# LibreSolar_BMS48V_0.net
KiCad netlist of a schematic drawn in Altium Designer
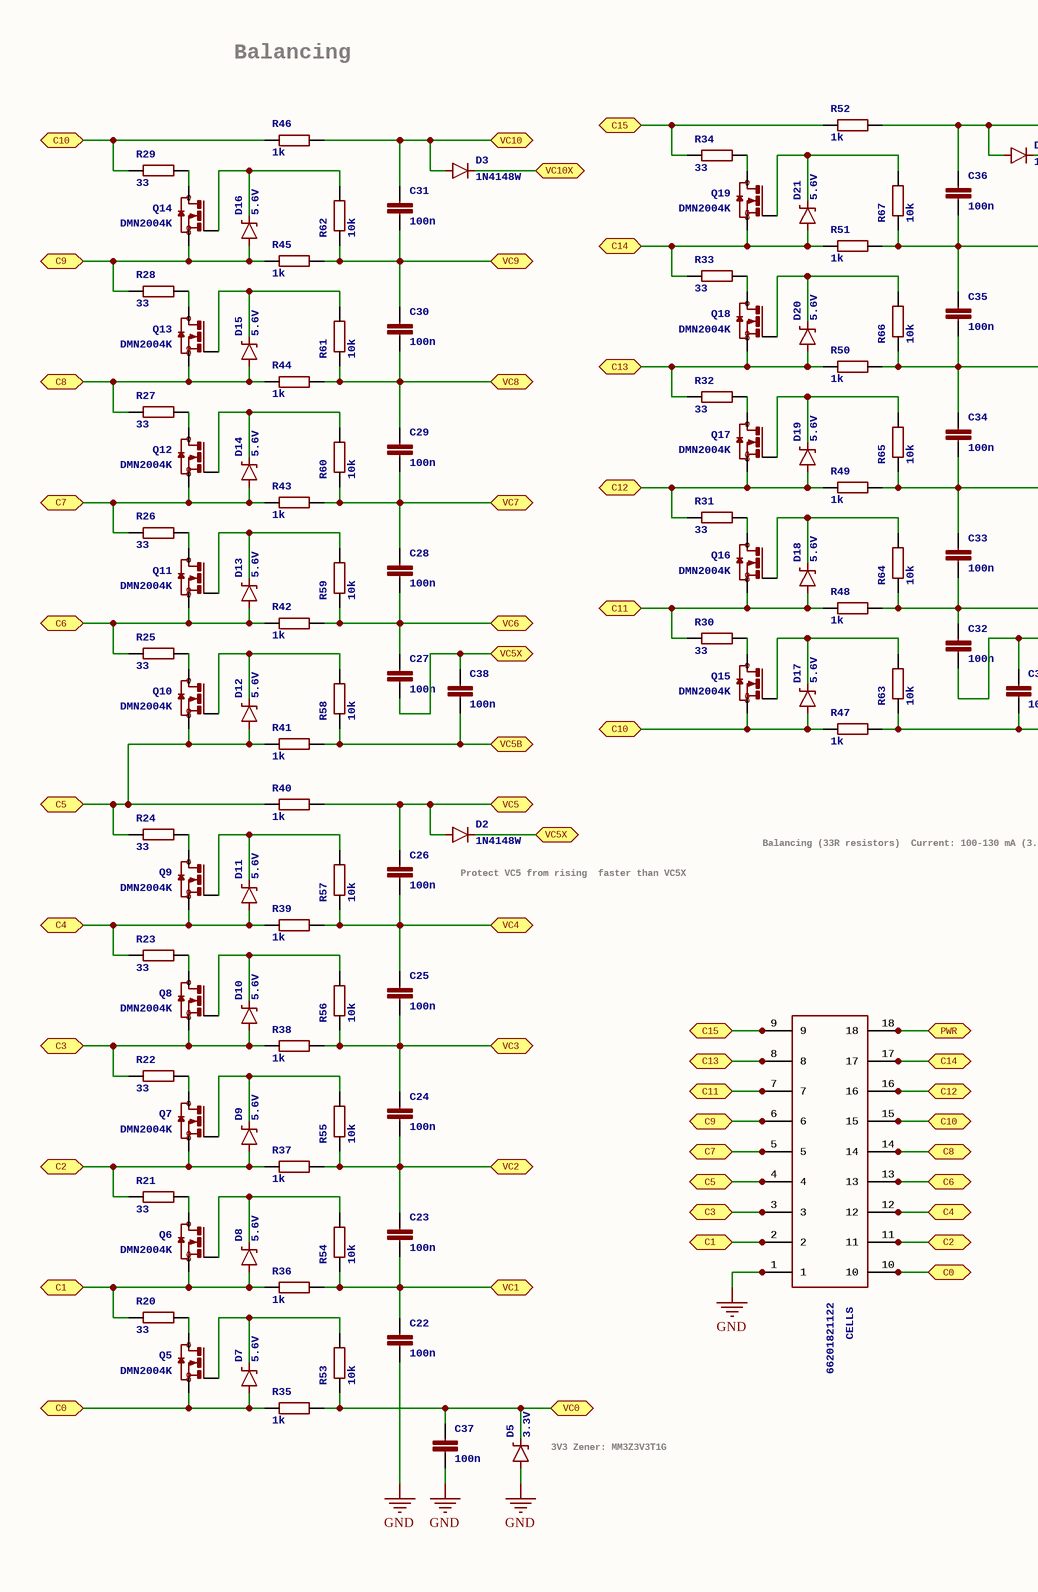
[diagram p0: LibreSolar_BMS48V_0.SchDoc, left]
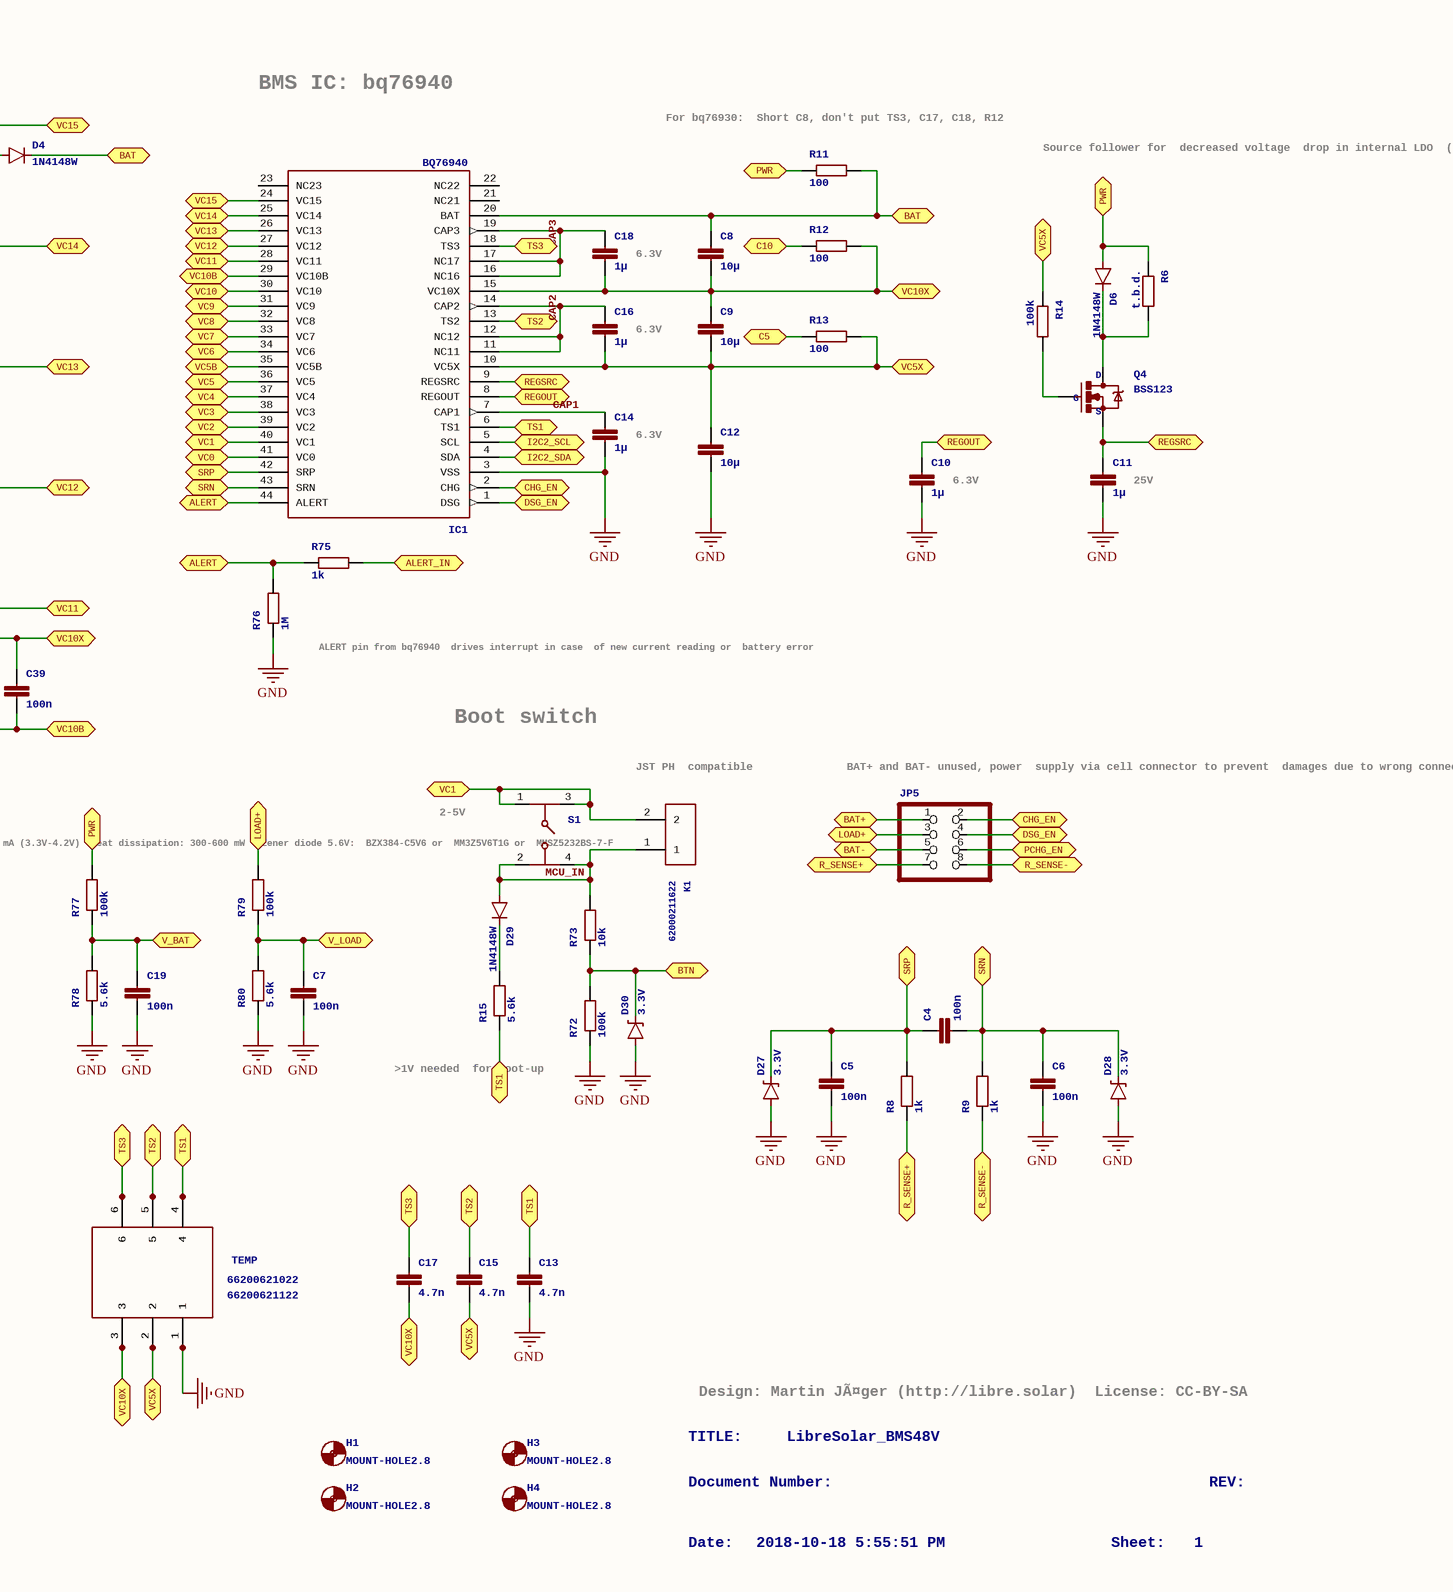
[diagram p1: LibreSolar_BMS48V_0.SchDoc, right]

(export (version "E")
  (design (tool "Eeschema 10.0.6"))
  (components
    (comp (ref "C4")
      (value "100n")
      (footprint "C0603")
      (description "CAPACITOR, European symbol")
      (fields (field (name "MF") "WALSIN") (field (name "MPN") "0603B104K500CT"))
      (libsource (lib "") (part "C-EUC0603_1"))
    )
    (comp (ref "C5")
      (value "100n")
      (footprint "C0603")
      (description "CAPACITOR, European symbol")
      (fields (field (name "MF") "WALSIN") (field (name "MPN") "0603B104K500CT"))
      (libsource (lib "rcl") (part "C-EUC0603"))
    )
    (comp (ref "C6")
      (value "100n")
      (footprint "C0603")
      (description "CAPACITOR, European symbol")
      (fields (field (name "MF") "WALSIN") (field (name "MPN") "0603B104K500CT"))
      (libsource (lib "rcl") (part "C-EUC0603"))
    )
    (comp (ref "C7")
      (value "100n")
      (footprint "C0603")
      (description "CAPACITOR, European symbol")
      (fields (field (name "MF") "WALSIN") (field (name "MPN") "0603B104K500CT"))
      (libsource (lib "rcl") (part "C-EUC0603"))
    )
    (comp (ref "C8")
      (value "10µ")
      (footprint "C1210")
      (description "CAPACITOR, European symbol")
      (fields (field (name "MF") "MURATA") (field (name "MPN") "GRM32ER7YA106KA12L"))
      (libsource (lib "rcl") (part "C-EUC1210"))
    )
    (comp (ref "C9")
      (value "10µ")
      (footprint "C1210")
      (description "CAPACITOR, European symbol")
      (fields (field (name "MF") "MURATA") (field (name "MPN") "GRM32ER7YA106KA12L"))
      (libsource (lib "rcl") (part "C-EUC1210"))
    )
    (comp (ref "C10")
      (value "1µ")
      (footprint "C0603")
      (description "CAPACITOR, European symbol")
      (fields (field (name "MF") "AVX") (field (name "MPN") "0805YC475KAT2A"))
      (libsource (lib "rcl") (part "C-EUC0603"))
    )
    (comp (ref "C11")
      (value "1µ")
      (footprint "C0603")
      (description "CAPACITOR, European symbol")
      (fields (field (name "MF") "MURATA") (field (name "MPN") "GRM188R71E105KA12D"))
      (libsource (lib "rcl") (part "C-EUC0603"))
    )
    (comp (ref "C12")
      (value "10µ")
      (footprint "C1210")
      (description "CAPACITOR, European symbol")
      (fields (field (name "MF") "MURATA") (field (name "MPN") "GRM32ER7YA106KA12L"))
      (libsource (lib "rcl") (part "C-EUC1210"))
    )
    (comp (ref "C13")
      (value "4.7n")
      (footprint "C0603")
      (description "CAPACITOR, European symbol")
      (fields (field (name "MF") "WALSIN") (field (name "MPN") "0603B104K500CT"))
      (libsource (lib "rcl") (part "C-EUC0603"))
    )
    (comp (ref "C14")
      (value "1µ")
      (footprint "C0603")
      (description "CAPACITOR, European symbol")
      (fields (field (name "MF") "MURATA") (field (name "MPN") "GRM188R71E105KA12D"))
      (libsource (lib "rcl") (part "C-EUC0603"))
    )
    (comp (ref "C15")
      (value "4.7n")
      (footprint "C0603")
      (description "CAPACITOR, European symbol")
      (fields (field (name "MF") "WALSIN") (field (name "MPN") "0603B104K500CT"))
      (libsource (lib "rcl") (part "C-EUC0603"))
    )
    (comp (ref "C16")
      (value "1µ")
      (footprint "C0603")
      (description "CAPACITOR, European symbol")
      (fields (field (name "MF") "MURATA") (field (name "MPN") "GRM188R71E105KA12D"))
      (libsource (lib "rcl") (part "C-EUC0603"))
    )
    (comp (ref "C17")
      (value "4.7n")
      (footprint "C0603")
      (description "CAPACITOR, European symbol")
      (fields (field (name "MF") "WALSIN") (field (name "MPN") "0603B104K500CT"))
      (libsource (lib "rcl") (part "C-EUC0603"))
    )
    (comp (ref "C18")
      (value "1µ")
      (footprint "C0603")
      (description "CAPACITOR, European symbol")
      (fields (field (name "MF") "MURATA") (field (name "MPN") "GRM188R71E105KA12D"))
      (libsource (lib "rcl") (part "C-EUC0603"))
    )
    (comp (ref "C19")
      (value "100n")
      (footprint "C0603")
      (description "CAPACITOR, European symbol")
      (fields (field (name "MF") "WALSIN") (field (name "MPN") "0603B104K500CT"))
      (libsource (lib "rcl") (part "C-EUC0603"))
    )
    (comp (ref "C22")
      (value "100n")
      (footprint "C0603")
      (description "CAPACITOR, European symbol")
      (fields (field (name "MF") "WALSIN") (field (name "MPN") "0603B104K500CT"))
      (libsource (lib "rcl") (part "C-EUC0603"))
    )
    (comp (ref "C23")
      (value "100n")
      (footprint "C0603")
      (description "CAPACITOR, European symbol")
      (fields (field (name "MF") "WALSIN") (field (name "MPN") "0603B104K500CT"))
      (libsource (lib "rcl") (part "C-EUC0603"))
    )
    (comp (ref "C24")
      (value "100n")
      (footprint "C0603")
      (description "CAPACITOR, European symbol")
      (fields (field (name "MF") "WALSIN") (field (name "MPN") "0603B104K500CT"))
      (libsource (lib "rcl") (part "C-EUC0603"))
    )
    (comp (ref "C25")
      (value "100n")
      (footprint "C0603")
      (description "CAPACITOR, European symbol")
      (fields (field (name "MF") "WALSIN") (field (name "MPN") "0603B104K500CT"))
      (libsource (lib "rcl") (part "C-EUC0603"))
    )
    (comp (ref "C26")
      (value "100n")
      (footprint "C0603")
      (description "CAPACITOR, European symbol")
      (fields (field (name "MF") "WALSIN") (field (name "MPN") "0603B104K500CT"))
      (libsource (lib "rcl") (part "C-EUC0603"))
    )
    (comp (ref "C27")
      (value "100n")
      (footprint "C0603")
      (description "CAPACITOR, European symbol")
      (fields (field (name "MF") "WALSIN") (field (name "MPN") "0603B104K500CT"))
      (libsource (lib "rcl") (part "C-EUC0603"))
    )
    (comp (ref "C28")
      (value "100n")
      (footprint "C0603")
      (description "CAPACITOR, European symbol")
      (fields (field (name "MF") "WALSIN") (field (name "MPN") "0603B104K500CT"))
      (libsource (lib "rcl") (part "C-EUC0603"))
    )
    (comp (ref "C29")
      (value "100n")
      (footprint "C0603")
      (description "CAPACITOR, European symbol")
      (fields (field (name "MF") "WALSIN") (field (name "MPN") "0603B104K500CT"))
      (libsource (lib "rcl") (part "C-EUC0603"))
    )
    (comp (ref "C30")
      (value "100n")
      (footprint "C0603")
      (description "CAPACITOR, European symbol")
      (fields (field (name "MF") "WALSIN") (field (name "MPN") "0603B104K500CT"))
      (libsource (lib "rcl") (part "C-EUC0603"))
    )
    (comp (ref "C31")
      (value "100n")
      (footprint "C0603")
      (description "CAPACITOR, European symbol")
      (fields (field (name "MF") "WALSIN") (field (name "MPN") "0603B104K500CT"))
      (libsource (lib "rcl") (part "C-EUC0603"))
    )
    (comp (ref "C32")
      (value "100n")
      (footprint "C0603")
      (description "CAPACITOR, European symbol")
      (fields (field (name "MF") "WALSIN") (field (name "MPN") "0603B104K500CT"))
      (libsource (lib "rcl") (part "C-EUC0603"))
    )
    (comp (ref "C33")
      (value "100n")
      (footprint "C0603")
      (description "CAPACITOR, European symbol")
      (fields (field (name "MF") "WALSIN") (field (name "MPN") "0603B104K500CT"))
      (libsource (lib "rcl") (part "C-EUC0603"))
    )
    (comp (ref "C34")
      (value "100n")
      (footprint "C0603")
      (description "CAPACITOR, European symbol")
      (fields (field (name "MF") "WALSIN") (field (name "MPN") "0603B104K500CT"))
      (libsource (lib "rcl") (part "C-EUC0603"))
    )
    (comp (ref "C35")
      (value "100n")
      (footprint "C0603")
      (description "CAPACITOR, European symbol")
      (fields (field (name "MF") "WALSIN") (field (name "MPN") "0603B104K500CT"))
      (libsource (lib "rcl") (part "C-EUC0603"))
    )
    (comp (ref "C36")
      (value "100n")
      (footprint "C0603")
      (description "CAPACITOR, European symbol")
      (fields (field (name "MF") "WALSIN") (field (name "MPN") "0603B104K500CT"))
      (libsource (lib "rcl") (part "C-EUC0603"))
    )
    (comp (ref "C37")
      (value "100n")
      (footprint "C0603")
      (description "CAPACITOR, European symbol")
      (fields (field (name "MF") "WALSIN") (field (name "MPN") "0603B104K500CT"))
      (libsource (lib "rcl") (part "C-EUC0603"))
    )
    (comp (ref "C38")
      (value "100n")
      (footprint "C0603")
      (description "CAPACITOR, European symbol")
      (fields (field (name "MF") "WALSIN") (field (name "MPN") "0603B104K500CT"))
      (libsource (lib "rcl") (part "C-EUC0603"))
    )
    (comp (ref "C39")
      (value "100n")
      (footprint "C0603")
      (description "CAPACITOR, European symbol")
      (fields (field (name "MF") "WALSIN") (field (name "MPN") "0603B104K500CT"))
      (libsource (lib "rcl") (part "C-EUC0603"))
    )
    (comp (ref "CELLS")
      (value "66201821022")
      (footprint "66201821022")
      (libsource (lib "Wire_to_Board_Connectors_rev15d") (part "66201821022"))
    )
    (comp (ref "D2")
      (value "1N4148W")
      (footprint "SOD-123")
      (fields (field (name "MF") "DIODES INC.") (field (name "MPN") "1N4148W-7-F."))
      (libsource (lib "SparkFun-DiscreteSemi") (part "DIODESOD123"))
    )
    (comp (ref "D3")
      (value "1N4148W")
      (footprint "SOD-123")
      (fields (field (name "MF") "DIODES INC.") (field (name "MPN") "1N4148W-7-F."))
      (libsource (lib "SparkFun-DiscreteSemi") (part "DIODESOD123"))
    )
    (comp (ref "D4")
      (value "1N4148W")
      (footprint "SOD-123")
      (fields (field (name "MF") "DIODES INC.") (field (name "MPN") "1N4148W-7-F."))
      (libsource (lib "SparkFun-DiscreteSemi") (part "DIODESOD123"))
    )
    (comp (ref "D5")
      (value "3.3V")
      (footprint "SOD-323")
      (description "Zener Diode Production Part - 8199 3.4V Zener Voltage")
      (fields (field (name "MF") "NXP") (field (name "MPN") "BZX384-C5V6"))
      (libsource (lib "SparkFun-DiscreteSemi") (part "DIODE-ZENER5.6V"))
    )
    (comp (ref "D6")
      (value "1N4148W")
      (footprint "SOD-123")
      (fields (field (name "MF") "DIODES INC.") (field (name "MPN") "1N4148W-7-F."))
      (libsource (lib "SparkFun-DiscreteSemi") (part "DIODESOD123"))
    )
    (comp (ref "D7")
      (value "5.6V")
      (footprint "SOD-323")
      (description "Zener Diode Production Part - 8199 3.4V Zener Voltage")
      (fields (field (name "MF") "NXP") (field (name "MPN") "BZX384-C5V6"))
      (libsource (lib "SparkFun-DiscreteSemi") (part "DIODE-ZENER5.6V"))
    )
    (comp (ref "D8")
      (value "5.6V")
      (footprint "SOD-323")
      (description "Zener Diode Production Part - 8199 3.4V Zener Voltage")
      (fields (field (name "MF") "NXP") (field (name "MPN") "BZX384-C5V6"))
      (libsource (lib "SparkFun-DiscreteSemi") (part "DIODE-ZENER5.6V"))
    )
    (comp (ref "D9")
      (value "5.6V")
      (footprint "SOD-323")
      (description "Zener Diode Production Part - 8199 3.4V Zener Voltage")
      (fields (field (name "MF") "NXP") (field (name "MPN") "BZX384-C5V6"))
      (libsource (lib "SparkFun-DiscreteSemi") (part "DIODE-ZENER5.6V"))
    )
    (comp (ref "D10")
      (value "5.6V")
      (footprint "SOD-323")
      (description "Zener Diode Production Part - 8199 3.4V Zener Voltage")
      (fields (field (name "MF") "NXP") (field (name "MPN") "BZX384-C5V6"))
      (libsource (lib "SparkFun-DiscreteSemi") (part "DIODE-ZENER5.6V"))
    )
    (comp (ref "D11")
      (value "5.6V")
      (footprint "SOD-323")
      (description "Zener Diode Production Part - 8199 3.4V Zener Voltage")
      (fields (field (name "MF") "NXP") (field (name "MPN") "BZX384-C5V6"))
      (libsource (lib "SparkFun-DiscreteSemi") (part "DIODE-ZENER5.6V"))
    )
    (comp (ref "D12")
      (value "5.6V")
      (footprint "SOD-323")
      (description "Zener Diode Production Part - 8199 3.4V Zener Voltage")
      (fields (field (name "MF") "NXP") (field (name "MPN") "BZX384-C5V6"))
      (libsource (lib "SparkFun-DiscreteSemi") (part "DIODE-ZENER5.6V"))
    )
    (comp (ref "D13")
      (value "5.6V")
      (footprint "SOD-323")
      (description "Zener Diode Production Part - 8199 3.4V Zener Voltage")
      (fields (field (name "MF") "NXP") (field (name "MPN") "BZX384-C5V6"))
      (libsource (lib "SparkFun-DiscreteSemi") (part "DIODE-ZENER5.6V"))
    )
    (comp (ref "D14")
      (value "5.6V")
      (footprint "SOD-323")
      (description "Zener Diode Production Part - 8199 3.4V Zener Voltage")
      (fields (field (name "MF") "NXP") (field (name "MPN") "BZX384-C5V6"))
      (libsource (lib "SparkFun-DiscreteSemi") (part "DIODE-ZENER5.6V"))
    )
    (comp (ref "D15")
      (value "5.6V")
      (footprint "SOD-323")
      (description "Zener Diode Production Part - 8199 3.4V Zener Voltage")
      (fields (field (name "MF") "NXP") (field (name "MPN") "BZX384-C5V6"))
      (libsource (lib "SparkFun-DiscreteSemi") (part "DIODE-ZENER5.6V"))
    )
    (comp (ref "D16")
      (value "5.6V")
      (footprint "SOD-323")
      (description "Zener Diode Production Part - 8199 3.4V Zener Voltage")
      (fields (field (name "MF") "NXP") (field (name "MPN") "BZX384-C5V6"))
      (libsource (lib "SparkFun-DiscreteSemi") (part "DIODE-ZENER5.6V"))
    )
    (comp (ref "D17")
      (value "5.6V")
      (footprint "SOD-323")
      (description "Zener Diode Production Part - 8199 3.4V Zener Voltage")
      (fields (field (name "MF") "NXP") (field (name "MPN") "BZX384-C5V6"))
      (libsource (lib "SparkFun-DiscreteSemi") (part "DIODE-ZENER5.6V"))
    )
    (comp (ref "D18")
      (value "5.6V")
      (footprint "SOD-323")
      (description "Zener Diode Production Part - 8199 3.4V Zener Voltage")
      (fields (field (name "MF") "NXP") (field (name "MPN") "BZX384-C5V6"))
      (libsource (lib "SparkFun-DiscreteSemi") (part "DIODE-ZENER5.6V"))
    )
    (comp (ref "D19")
      (value "5.6V")
      (footprint "SOD-323")
      (description "Zener Diode Production Part - 8199 3.4V Zener Voltage")
      (fields (field (name "MF") "NXP") (field (name "MPN") "BZX384-C5V6"))
      (libsource (lib "SparkFun-DiscreteSemi") (part "DIODE-ZENER5.6V"))
    )
    (comp (ref "D20")
      (value "5.6V")
      (footprint "SOD-323")
      (description "Zener Diode Production Part - 8199 3.4V Zener Voltage")
      (fields (field (name "MF") "NXP") (field (name "MPN") "BZX384-C5V6"))
      (libsource (lib "SparkFun-DiscreteSemi") (part "DIODE-ZENER5.6V"))
    )
    (comp (ref "D21")
      (value "5.6V")
      (footprint "SOD-323")
      (description "Zener Diode Production Part - 8199 3.4V Zener Voltage")
      (fields (field (name "MF") "NXP") (field (name "MPN") "BZX384-C5V6"))
      (libsource (lib "SparkFun-DiscreteSemi") (part "DIODE-ZENER5.6V"))
    )
    (comp (ref "D27")
      (value "3.3V")
      (footprint "SOD-323")
      (description "Zener Diode Production Part - 8199 3.4V Zener Voltage")
      (fields (field (name "MF") "NXP") (field (name "MPN") "BZX384-C5V6"))
      (libsource (lib "SparkFun-DiscreteSemi") (part "DIODE-ZENER5.6V"))
    )
    (comp (ref "D28")
      (value "3.3V")
      (footprint "SOD-323")
      (description "Zener Diode Production Part - 8199 3.4V Zener Voltage")
      (fields (field (name "MF") "NXP") (field (name "MPN") "BZX384-C5V6"))
      (libsource (lib "SparkFun-DiscreteSemi") (part "DIODE-ZENER5.6V"))
    )
    (comp (ref "D29")
      (value "1N4148W")
      (footprint "SOD-123")
      (fields (field (name "MF") "DIODES INC.") (field (name "MPN") "1N4148W-7-F."))
      (libsource (lib "SparkFun-DiscreteSemi") (part "DIODESOD123"))
    )
    (comp (ref "D30")
      (value "3.3V")
      (footprint "SOD-323")
      (description "Zener Diode Production Part - 8199 3.4V Zener Voltage")
      (fields (field (name "MF") "NXP") (field (name "MPN") "BZX384-C5V6"))
      (libsource (lib "SparkFun-DiscreteSemi") (part "DIODE-ZENER5.6V"))
    )
    (comp (ref "H1")
      (value "MOUNT-HOLE2.8")
      (footprint "2,8")
      (description "MOUNTING HOLE with drill center marker")
      (libsource (lib "holes") (part "MOUNT-HOLE2.8"))
    )
    (comp (ref "H2")
      (value "MOUNT-HOLE2.8")
      (footprint "2,8")
      (description "MOUNTING HOLE with drill center marker")
      (libsource (lib "holes") (part "MOUNT-HOLE2.8"))
    )
    (comp (ref "H3")
      (value "MOUNT-HOLE2.8")
      (footprint "2,8")
      (description "MOUNTING HOLE with drill center marker")
      (libsource (lib "holes") (part "MOUNT-HOLE2.8"))
    )
    (comp (ref "H4")
      (value "MOUNT-HOLE2.8")
      (footprint "2,8")
      (description "MOUNTING HOLE with drill center marker")
      (libsource (lib "holes") (part "MOUNT-HOLE2.8"))
    )
    (comp (ref "IC1")
      (value "BQ76940")
      (footprint "TSSOP44")
      (fields (field (name "MF") "TEXAS INSTRUMENTS") (field (name "MPN") "BQ7694003DBT"))
      (libsource (lib "LibreSolar") (part "BQ76940"))
    )
    (comp (ref "JP5")
      (value "PINHD-2X4")
      (footprint "2X04")
      (description "PIN HEADER")
      (fields (field (name "LIBRARYNAME") "pinhead"))
      (libsource (lib "pinhead") (part "PINHD-2X4"))
    )
    (comp (ref "K1")
      (value "62000211622")
      (footprint "62000211622")
      (libsource (lib "Wire_to_Board_Connectors_rev15d") (part "62000211622"))
    )
    (comp (ref "K4")
      (value "66200621122")
      (footprint "66200621122")
      (libsource (lib "Wire_to_Board_Connectors_rev15d") (part "66200621122"))
    )
    (comp (ref "K5")
      (value "66201821122")
      (footprint "66201821122")
      (libsource (lib "Wire_to_Board_Connectors_rev15d") (part "66201821122"))
    )
    (comp (ref "Q4")
      (value "BSS123")
      (footprint "SOT23-3")
      (fields
        (field (name "MF") "NXP")
        (field (name "MPN") "2N7002,215")
        (field (name "D") "D")
        (field (name "S") "S")
        (field (name "G") "G")
      )
      (libsource (lib "SparkFun-DiscreteSemi") (part "MOSFET-NCHANNELBSS138"))
    )
    (comp (ref "Q5")
      (value "DMN2004K")
      (footprint "SOT23")
      (description "N-CHANNEL MOS FET with low VGS and ESD protection")
      (fields
        (field (name "MF") "DIODES INC.")
        (field (name "MPN") "DMN2004K-7")
        (field (name "LIBRARYNAME") "resolut")
      )
      (libsource (lib "resolut") (part "DMN2004K"))
    )
    (comp (ref "Q6")
      (value "DMN2004K")
      (footprint "SOT23")
      (description "N-CHANNEL MOS FET with low VGS and ESD protection")
      (fields
        (field (name "MF") "DIODES INC.")
        (field (name "MPN") "DMN2004K-7")
        (field (name "LIBRARYNAME") "resolut")
      )
      (libsource (lib "resolut") (part "DMN2004K"))
    )
    (comp (ref "Q7")
      (value "DMN2004K")
      (footprint "SOT23")
      (description "N-CHANNEL MOS FET with low VGS and ESD protection")
      (fields
        (field (name "MF") "DIODES INC.")
        (field (name "MPN") "DMN2004K-7")
        (field (name "LIBRARYNAME") "resolut")
      )
      (libsource (lib "resolut") (part "DMN2004K"))
    )
    (comp (ref "Q8")
      (value "DMN2004K")
      (footprint "SOT23")
      (description "N-CHANNEL MOS FET with low VGS and ESD protection")
      (fields
        (field (name "MF") "DIODES INC.")
        (field (name "MPN") "DMN2004K-7")
        (field (name "LIBRARYNAME") "resolut")
      )
      (libsource (lib "resolut") (part "DMN2004K"))
    )
    (comp (ref "Q9")
      (value "DMN2004K")
      (footprint "SOT23")
      (description "N-CHANNEL MOS FET with low VGS and ESD protection")
      (fields
        (field (name "MF") "DIODES INC.")
        (field (name "MPN") "DMN2004K-7")
        (field (name "LIBRARYNAME") "resolut")
      )
      (libsource (lib "resolut") (part "DMN2004K"))
    )
    (comp (ref "Q10")
      (value "DMN2004K")
      (footprint "SOT23")
      (description "N-CHANNEL MOS FET with low VGS and ESD protection")
      (fields
        (field (name "MF") "DIODES INC.")
        (field (name "MPN") "DMN2004K-7")
        (field (name "LIBRARYNAME") "resolut")
      )
      (libsource (lib "resolut") (part "DMN2004K"))
    )
    (comp (ref "Q11")
      (value "DMN2004K")
      (footprint "SOT23")
      (description "N-CHANNEL MOS FET with low VGS and ESD protection")
      (fields
        (field (name "MF") "DIODES INC.")
        (field (name "MPN") "DMN2004K-7")
        (field (name "LIBRARYNAME") "resolut")
      )
      (libsource (lib "resolut") (part "DMN2004K"))
    )
    (comp (ref "Q12")
      (value "DMN2004K")
      (footprint "SOT23")
      (description "N-CHANNEL MOS FET with low VGS and ESD protection")
      (fields
        (field (name "MF") "DIODES INC.")
        (field (name "MPN") "DMN2004K-7")
        (field (name "LIBRARYNAME") "resolut")
      )
      (libsource (lib "resolut") (part "DMN2004K"))
    )
    (comp (ref "Q13")
      (value "DMN2004K")
      (footprint "SOT23")
      (description "N-CHANNEL MOS FET with low VGS and ESD protection")
      (fields
        (field (name "MF") "DIODES INC.")
        (field (name "MPN") "DMN2004K-7")
        (field (name "LIBRARYNAME") "resolut")
      )
      (libsource (lib "resolut") (part "DMN2004K"))
    )
    (comp (ref "Q14")
      (value "DMN2004K")
      (footprint "SOT23")
      (description "N-CHANNEL MOS FET with low VGS and ESD protection")
      (fields
        (field (name "MF") "DIODES INC.")
        (field (name "MPN") "DMN2004K-7")
        (field (name "LIBRARYNAME") "resolut")
      )
      (libsource (lib "resolut") (part "DMN2004K"))
    )
    (comp (ref "Q15")
      (value "DMN2004K")
      (footprint "SOT23")
      (description "N-CHANNEL MOS FET with low VGS and ESD protection")
      (fields
        (field (name "MF") "DIODES INC.")
        (field (name "MPN") "DMN2004K-7")
        (field (name "LIBRARYNAME") "resolut")
      )
      (libsource (lib "resolut") (part "DMN2004K"))
    )
    (comp (ref "Q16")
      (value "DMN2004K")
      (footprint "SOT23")
      (description "N-CHANNEL MOS FET with low VGS and ESD protection")
      (fields
        (field (name "MF") "DIODES INC.")
        (field (name "MPN") "DMN2004K-7")
        (field (name "LIBRARYNAME") "resolut")
      )
      (libsource (lib "resolut") (part "DMN2004K"))
    )
    (comp (ref "Q17")
      (value "DMN2004K")
      (footprint "SOT23")
      (description "N-CHANNEL MOS FET with low VGS and ESD protection")
      (fields
        (field (name "MF") "DIODES INC.")
        (field (name "MPN") "DMN2004K-7")
        (field (name "LIBRARYNAME") "resolut")
      )
      (libsource (lib "resolut") (part "DMN2004K"))
    )
    (comp (ref "Q18")
      (value "DMN2004K")
      (footprint "SOT23")
      (description "N-CHANNEL MOS FET with low VGS and ESD protection")
      (fields
        (field (name "MF") "DIODES INC.")
        (field (name "MPN") "DMN2004K-7")
        (field (name "LIBRARYNAME") "resolut")
      )
      (libsource (lib "resolut") (part "DMN2004K"))
    )
    (comp (ref "Q19")
      (value "DMN2004K")
      (footprint "SOT23")
      (description "N-CHANNEL MOS FET with low VGS and ESD protection")
      (fields
        (field (name "MF") "DIODES INC.")
        (field (name "MPN") "DMN2004K-7")
        (field (name "LIBRARYNAME") "resolut")
      )
      (libsource (lib "resolut") (part "DMN2004K"))
    )
    (comp (ref "R6")
      (value "t.b.d.")
      (footprint "R0603")
      (description "RESISTOR, European symbol")
      (fields (field (name "MF") "MULTICOMP") (field (name "MPN") "MCMR06X1001FTL"))
      (libsource (lib "rcl") (part "R-EU_R0603"))
    )
    (comp (ref "R8")
      (value "1k")
      (footprint "R0603")
      (description "RESISTOR, European symbol")
      (fields (field (name "MF") "MULTICOMP") (field (name "MPN") "MCMR06X1001FTL"))
      (libsource (lib "rcl") (part "R-EU_R0603"))
    )
    (comp (ref "R9")
      (value "1k")
      (footprint "R0603")
      (description "RESISTOR, European symbol")
      (fields (field (name "MF") "MULTICOMP") (field (name "MPN") "MCMR06X1001FTL"))
      (libsource (lib "rcl") (part "R-EU_R0603"))
    )
    (comp (ref "R11")
      (value "100")
      (footprint "R0603")
      (description "RESISTOR, European symbol")
      (fields (field (name "MF") "MULTICOMP") (field (name "MPN") "MCMR06X1001FTL"))
      (libsource (lib "rcl") (part "R-EU_R0603"))
    )
    (comp (ref "R12")
      (value "100")
      (footprint "R0603")
      (description "RESISTOR, European symbol")
      (fields (field (name "MF") "MULTICOMP") (field (name "MPN") "MCMR06X1001FTL"))
      (libsource (lib "rcl") (part "R-EU_R0603"))
    )
    (comp (ref "R13")
      (value "100")
      (footprint "R0603")
      (description "RESISTOR, European symbol")
      (fields (field (name "MF") "MULTICOMP") (field (name "MPN") "MCMR06X1001FTL"))
      (libsource (lib "rcl") (part "R-EU_R0603"))
    )
    (comp (ref "R14")
      (value "100k")
      (footprint "R0603")
      (description "RESISTOR, European symbol")
      (libsource (lib "rcl") (part "R-EU_R0603"))
    )
    (comp (ref "R15")
      (value "5.6k")
      (footprint "R0603")
      (description "RESISTOR, European symbol")
      (fields (field (name "MF") "MULTICOMP") (field (name "MPN") "MCMR06X1001FTL"))
      (libsource (lib "rcl") (part "R-EU_R0603"))
    )
    (comp (ref "R20")
      (value "33")
      (footprint "R2010")
      (description "RESISTOR, European symbol")
      (fields (field (name "MF") "WELWYN") (field (name "MPN") "ASC2010-33RFT4"))
      (libsource (lib "rcl") (part "R-EU_R2010"))
    )
    (comp (ref "R21")
      (value "33")
      (footprint "R2010")
      (description "RESISTOR, European symbol")
      (fields (field (name "MF") "WELWYN") (field (name "MPN") "ASC2010-33RFT4"))
      (libsource (lib "rcl") (part "R-EU_R2010"))
    )
    (comp (ref "R22")
      (value "33")
      (footprint "R2010")
      (description "RESISTOR, European symbol")
      (fields (field (name "MF") "WELWYN") (field (name "MPN") "ASC2010-33RFT4"))
      (libsource (lib "rcl") (part "R-EU_R2010"))
    )
    (comp (ref "R23")
      (value "33")
      (footprint "R2010")
      (description "RESISTOR, European symbol")
      (fields (field (name "MF") "WELWYN") (field (name "MPN") "ASC2010-33RFT4"))
      (libsource (lib "rcl") (part "R-EU_R2010"))
    )
    (comp (ref "R24")
      (value "33")
      (footprint "R2010")
      (description "RESISTOR, European symbol")
      (fields (field (name "MF") "WELWYN") (field (name "MPN") "ASC2010-33RFT4"))
      (libsource (lib "rcl") (part "R-EU_R2010"))
    )
    (comp (ref "R25")
      (value "33")
      (footprint "R2010")
      (description "RESISTOR, European symbol")
      (fields (field (name "MF") "WELWYN") (field (name "MPN") "ASC2010-33RFT4"))
      (libsource (lib "rcl") (part "R-EU_R2010"))
    )
    (comp (ref "R26")
      (value "33")
      (footprint "R2010")
      (description "RESISTOR, European symbol")
      (fields (field (name "MF") "WELWYN") (field (name "MPN") "ASC2010-33RFT4"))
      (libsource (lib "rcl") (part "R-EU_R2010"))
    )
    (comp (ref "R27")
      (value "33")
      (footprint "R2010")
      (description "RESISTOR, European symbol")
      (fields (field (name "MF") "WELWYN") (field (name "MPN") "ASC2010-33RFT4"))
      (libsource (lib "rcl") (part "R-EU_R2010"))
    )
    (comp (ref "R28")
      (value "33")
      (footprint "R2010")
      (description "RESISTOR, European symbol")
      (fields (field (name "MF") "WELWYN") (field (name "MPN") "ASC2010-33RFT4"))
      (libsource (lib "rcl") (part "R-EU_R2010"))
    )
    (comp (ref "R29")
      (value "33")
      (footprint "R2010")
      (description "RESISTOR, European symbol")
      (fields (field (name "MF") "WELWYN") (field (name "MPN") "ASC2010-33RFT4"))
      (libsource (lib "rcl") (part "R-EU_R2010"))
    )
    (comp (ref "R30")
      (value "33")
      (footprint "R2010")
      (description "RESISTOR, European symbol")
      (fields (field (name "MF") "WELWYN") (field (name "MPN") "ASC2010-33RFT4"))
      (libsource (lib "rcl") (part "R-EU_R2010"))
    )
    (comp (ref "R31")
      (value "33")
      (footprint "R2010")
      (description "RESISTOR, European symbol")
      (fields (field (name "MF") "WELWYN") (field (name "MPN") "ASC2010-33RFT4"))
      (libsource (lib "rcl") (part "R-EU_R2010"))
    )
    (comp (ref "R32")
      (value "33")
      (footprint "R2010")
      (description "RESISTOR, European symbol")
      (fields (field (name "MF") "WELWYN") (field (name "MPN") "ASC2010-33RFT4"))
      (libsource (lib "rcl") (part "R-EU_R2010"))
    )
    (comp (ref "R33")
      (value "33")
      (footprint "R2010")
      (description "RESISTOR, European symbol")
      (fields (field (name "MF") "WELWYN") (field (name "MPN") "ASC2010-33RFT4"))
      (libsource (lib "rcl") (part "R-EU_R2010"))
    )
    (comp (ref "R34")
      (value "33")
      (footprint "R2010")
      (description "RESISTOR, European symbol")
      (fields (field (name "MF") "WELWYN") (field (name "MPN") "ASC2010-33RFT4"))
      (libsource (lib "rcl") (part "R-EU_R2010"))
    )
    (comp (ref "R35")
      (value "1k")
      (footprint "R0603")
      (description "RESISTOR, European symbol")
      (fields (field (name "MF") "MULTICOMP") (field (name "MPN") "MCMR06X1001FTL"))
      (libsource (lib "rcl") (part "R-EU_R0603"))
    )
    (comp (ref "R36")
      (value "1k")
      (footprint "R0603")
      (description "RESISTOR, European symbol")
      (fields (field (name "MF") "MULTICOMP") (field (name "MPN") "MCMR06X1001FTL"))
      (libsource (lib "rcl") (part "R-EU_R0603"))
    )
    (comp (ref "R37")
      (value "1k")
      (footprint "R0603")
      (description "RESISTOR, European symbol")
      (fields (field (name "MF") "MULTICOMP") (field (name "MPN") "MCMR06X1001FTL"))
      (libsource (lib "rcl") (part "R-EU_R0603"))
    )
    (comp (ref "R38")
      (value "1k")
      (footprint "R0603")
      (description "RESISTOR, European symbol")
      (fields (field (name "MF") "MULTICOMP") (field (name "MPN") "MCMR06X1001FTL"))
      (libsource (lib "rcl") (part "R-EU_R0603"))
    )
    (comp (ref "R39")
      (value "1k")
      (footprint "R0603")
      (description "RESISTOR, European symbol")
      (fields (field (name "MF") "MULTICOMP") (field (name "MPN") "MCMR06X1001FTL"))
      (libsource (lib "rcl") (part "R-EU_R0603"))
    )
    (comp (ref "R40")
      (value "1k")
      (footprint "R0603")
      (description "RESISTOR, European symbol")
      (fields (field (name "MF") "MULTICOMP") (field (name "MPN") "MCMR06X1001FTL"))
      (libsource (lib "rcl") (part "R-EU_R0603"))
    )
    (comp (ref "R41")
      (value "1k")
      (footprint "R0603")
      (description "RESISTOR, European symbol")
      (fields (field (name "MF") "MULTICOMP") (field (name "MPN") "MCMR06X1001FTL"))
      (libsource (lib "rcl") (part "R-EU_R0603"))
    )
    (comp (ref "R42")
      (value "1k")
      (footprint "R0603")
      (description "RESISTOR, European symbol")
      (fields (field (name "MF") "MULTICOMP") (field (name "MPN") "MCMR06X1001FTL"))
      (libsource (lib "rcl") (part "R-EU_R0603"))
    )
    (comp (ref "R43")
      (value "1k")
      (footprint "R0603")
      (description "RESISTOR, European symbol")
      (fields (field (name "MF") "MULTICOMP") (field (name "MPN") "MCMR06X1001FTL"))
      (libsource (lib "rcl") (part "R-EU_R0603"))
    )
    (comp (ref "R44")
      (value "1k")
      (footprint "R0603")
      (description "RESISTOR, European symbol")
      (fields (field (name "MF") "MULTICOMP") (field (name "MPN") "MCMR06X1001FTL"))
      (libsource (lib "rcl") (part "R-EU_R0603"))
    )
    (comp (ref "R45")
      (value "1k")
      (footprint "R0603")
      (description "RESISTOR, European symbol")
      (fields (field (name "MF") "MULTICOMP") (field (name "MPN") "MCMR06X1001FTL"))
      (libsource (lib "rcl") (part "R-EU_R0603"))
    )
    (comp (ref "R46")
      (value "1k")
      (footprint "R0603")
      (description "RESISTOR, European symbol")
      (fields (field (name "MF") "MULTICOMP") (field (name "MPN") "MCMR06X1001FTL"))
      (libsource (lib "rcl") (part "R-EU_R0603"))
    )
    (comp (ref "R47")
      (value "1k")
      (footprint "R0603")
      (description "RESISTOR, European symbol")
      (fields (field (name "MF") "MULTICOMP") (field (name "MPN") "MCMR06X1001FTL"))
      (libsource (lib "rcl") (part "R-EU_R0603"))
    )
    (comp (ref "R48")
      (value "1k")
      (footprint "R0603")
      (description "RESISTOR, European symbol")
      (fields (field (name "MF") "MULTICOMP") (field (name "MPN") "MCMR06X1001FTL"))
      (libsource (lib "rcl") (part "R-EU_R0603"))
    )
    (comp (ref "R49")
      (value "1k")
      (footprint "R0603")
      (description "RESISTOR, European symbol")
      (fields (field (name "MF") "MULTICOMP") (field (name "MPN") "MCMR06X1001FTL"))
      (libsource (lib "rcl") (part "R-EU_R0603"))
    )
    (comp (ref "R50")
      (value "1k")
      (footprint "R0603")
      (description "RESISTOR, European symbol")
      (fields (field (name "MF") "MULTICOMP") (field (name "MPN") "MCMR06X1001FTL"))
      (libsource (lib "rcl") (part "R-EU_R0603"))
    )
    (comp (ref "R51")
      (value "1k")
      (footprint "R0603")
      (description "RESISTOR, European symbol")
      (fields (field (name "MF") "MULTICOMP") (field (name "MPN") "MCMR06X1001FTL"))
      (libsource (lib "rcl") (part "R-EU_R0603"))
    )
    (comp (ref "R52")
      (value "1k")
      (footprint "R0603")
      (description "RESISTOR, European symbol")
      (fields (field (name "MF") "MULTICOMP") (field (name "MPN") "MCMR06X1001FTL"))
      (libsource (lib "rcl") (part "R-EU_R0603"))
    )
    (comp (ref "R53")
      (value "10k")
      (footprint "R0603")
      (description "RESISTOR, European symbol")
      (fields (field (name "MF") "PANASONIC ELECTRONIC COMPONENTS") (field (name "MPN") "ERJ3EKF1002V"))
      (libsource (lib "rcl") (part "R-EU_R0603"))
    )
    (comp (ref "R54")
      (value "10k")
      (footprint "R0603")
      (description "RESISTOR, European symbol")
      (fields (field (name "MF") "PANASONIC ELECTRONIC COMPONENTS") (field (name "MPN") "ERJ3EKF1002V"))
      (libsource (lib "rcl") (part "R-EU_R0603"))
    )
    (comp (ref "R55")
      (value "10k")
      (footprint "R0603")
      (description "RESISTOR, European symbol")
      (fields (field (name "MF") "PANASONIC ELECTRONIC COMPONENTS") (field (name "MPN") "ERJ3EKF1002V"))
      (libsource (lib "rcl") (part "R-EU_R0603"))
    )
    (comp (ref "R56")
      (value "10k")
      (footprint "R0603")
      (description "RESISTOR, European symbol")
      (fields (field (name "MF") "PANASONIC ELECTRONIC COMPONENTS") (field (name "MPN") "ERJ3EKF1002V"))
      (libsource (lib "rcl") (part "R-EU_R0603"))
    )
    (comp (ref "R57")
      (value "10k")
      (footprint "R0603")
      (description "RESISTOR, European symbol")
      (fields (field (name "MF") "PANASONIC ELECTRONIC COMPONENTS") (field (name "MPN") "ERJ3EKF1002V"))
      (libsource (lib "rcl") (part "R-EU_R0603"))
    )
    (comp (ref "R58")
      (value "10k")
      (footprint "R0603")
      (description "RESISTOR, European symbol")
      (fields (field (name "MF") "PANASONIC ELECTRONIC COMPONENTS") (field (name "MPN") "ERJ3EKF1002V"))
      (libsource (lib "rcl") (part "R-EU_R0603"))
    )
    (comp (ref "R59")
      (value "10k")
      (footprint "R0603")
      (description "RESISTOR, European symbol")
      (fields (field (name "MF") "PANASONIC ELECTRONIC COMPONENTS") (field (name "MPN") "ERJ3EKF1002V"))
      (libsource (lib "rcl") (part "R-EU_R0603"))
    )
    (comp (ref "R60")
      (value "10k")
      (footprint "R0603")
      (description "RESISTOR, European symbol")
      (fields (field (name "MF") "PANASONIC ELECTRONIC COMPONENTS") (field (name "MPN") "ERJ3EKF1002V"))
      (libsource (lib "rcl") (part "R-EU_R0603"))
    )
    (comp (ref "R61")
      (value "10k")
      (footprint "R0603")
      (description "RESISTOR, European symbol")
      (fields (field (name "MF") "PANASONIC ELECTRONIC COMPONENTS") (field (name "MPN") "ERJ3EKF1002V"))
      (libsource (lib "rcl") (part "R-EU_R0603"))
    )
    (comp (ref "R62")
      (value "10k")
      (footprint "R0603")
      (description "RESISTOR, European symbol")
      (fields (field (name "MF") "PANASONIC ELECTRONIC COMPONENTS") (field (name "MPN") "ERJ3EKF1002V"))
      (libsource (lib "rcl") (part "R-EU_R0603"))
    )
    (comp (ref "R63")
      (value "10k")
      (footprint "R0603")
      (description "RESISTOR, European symbol")
      (fields (field (name "MF") "PANASONIC ELECTRONIC COMPONENTS") (field (name "MPN") "ERJ3EKF1002V"))
      (libsource (lib "rcl") (part "R-EU_R0603"))
    )
    (comp (ref "R64")
      (value "10k")
      (footprint "R0603")
      (description "RESISTOR, European symbol")
      (fields (field (name "MF") "PANASONIC ELECTRONIC COMPONENTS") (field (name "MPN") "ERJ3EKF1002V"))
      (libsource (lib "rcl") (part "R-EU_R0603"))
    )
    (comp (ref "R65")
      (value "10k")
      (footprint "R0603")
      (description "RESISTOR, European symbol")
      (fields (field (name "MF") "PANASONIC ELECTRONIC COMPONENTS") (field (name "MPN") "ERJ3EKF1002V"))
      (libsource (lib "rcl") (part "R-EU_R0603"))
    )
    (comp (ref "R66")
      (value "10k")
      (footprint "R0603")
      (description "RESISTOR, European symbol")
      (fields (field (name "MF") "PANASONIC ELECTRONIC COMPONENTS") (field (name "MPN") "ERJ3EKF1002V"))
      (libsource (lib "rcl") (part "R-EU_R0603"))
    )
    (comp (ref "R67")
      (value "10k")
      (footprint "R0603")
      (description "RESISTOR, European symbol")
      (fields (field (name "MF") "PANASONIC ELECTRONIC COMPONENTS") (field (name "MPN") "ERJ3EKF1002V"))
      (libsource (lib "rcl") (part "R-EU_R0603"))
    )
    (comp (ref "R72")
      (value "100k")
      (footprint "R0603")
      (description "RESISTOR, European symbol")
      (fields (field (name "MF") "MULTICOMP") (field (name "MPN") "MCMR06X1001FTL"))
      (libsource (lib "rcl") (part "R-EU_R0603"))
    )
    (comp (ref "R73")
      (value "10k")
      (footprint "R0603")
      (description "RESISTOR, European symbol")
      (fields (field (name "MF") "MULTICOMP") (field (name "MPN") "MCMR06X1001FTL"))
      (libsource (lib "rcl") (part "R-EU_R0603"))
    )
    (comp (ref "R75")
      (value "1k")
      (footprint "R0603")
      (description "RESISTOR, European symbol")
      (fields (field (name "MF") "MULTICOMP") (field (name "MPN") "MCMR06X1001FTL"))
      (libsource (lib "rcl") (part "R-EU_R0603"))
    )
    (comp (ref "R76")
      (value "1M")
      (footprint "R0603")
      (description "RESISTOR, European symbol")
      (fields (field (name "MF") "PANASONIC ELECTRONIC COMPONENTS") (field (name "MPN") "ERJU06F1004V"))
      (libsource (lib "rcl") (part "R-EU_R0603"))
    )
    (comp (ref "R77")
      (value "100k")
      (footprint "R0603")
      (description "RESISTOR, European symbol")
      (fields (field (name "MF") "MULTICOMP") (field (name "MPN") "MCMR06X1001FTL"))
      (libsource (lib "rcl") (part "R-EU_R0603"))
    )
    (comp (ref "R78")
      (value "5.6k")
      (footprint "R0603")
      (description "RESISTOR, European symbol")
      (fields (field (name "MF") "MULTICOMP") (field (name "MPN") "MCMR06X1001FTL"))
      (libsource (lib "rcl") (part "R-EU_R0603"))
    )
    (comp (ref "R79")
      (value "100k")
      (footprint "R0603")
      (description "RESISTOR, European symbol")
      (fields (field (name "MF") "MULTICOMP") (field (name "MPN") "MCMR06X1001FTL"))
      (libsource (lib "rcl") (part "R-EU_R0603"))
    )
    (comp (ref "R80")
      (value "5.6k")
      (footprint "R0603")
      (description "RESISTOR, European symbol")
      (fields (field (name "MF") "MULTICOMP") (field (name "MPN") "MCMR06X1001FTL"))
      (libsource (lib "rcl") (part "R-EU_R0603"))
    )
    (comp (ref "S1")
      (value "430182050816")
      (footprint "430182050816")
      (fields (field (name "LIBRARYNAME") "EAGLE-TACT_SWITCHES-rev16e"))
      (libsource (lib "EAGLE-TACT_SWITCHES-rev16e") (part "430182050816"))
    )
    (comp (ref "TEMP")
      (value "66200621022")
      (footprint "66200621022")
      (libsource (lib "Wire_to_Board_Connectors_rev15d") (part "66200621022"))
    )
  )
  (nets
    (net (code "1") (name "/ALERT") (class "Default")
      (node (ref "IC1") (pin "44") (pinfunction "ALERT_44") (pintype "passive"))
      (node (ref "R75") (pin "1") (pinfunction "1_1") (pintype "passive"))
      (node (ref "R76") (pin "2") (pinfunction "2_2") (pintype "passive"))
    )
    (net (code "2") (name "/ALERT_IN") (class "Default")
      (node (ref "R75") (pin "2") (pinfunction "2_2") (pintype "passive"))
    )
    (net (code "3") (name "/BAT") (class "Default")
      (node (ref "C8") (pin "1") (pinfunction "1_1") (pintype "passive"))
      (node (ref "D4") (pin "C") (pinfunction "C_C") (pintype "passive"))
      (node (ref "IC1") (pin "20") (pinfunction "BAT_20") (pintype "power_in"))
      (node (ref "R11") (pin "2") (pinfunction "2_2") (pintype "passive"))
    )
    (net (code "4") (name "/BAT+") (class "Default")
      (node (ref "JP5") (pin "1") (pinfunction "1_1") (pintype "passive"))
    )
    (net (code "5") (name "/BAT-") (class "Default")
      (node (ref "JP5") (pin "5") (pinfunction "5_5") (pintype "passive"))
    )
    (net (code "6") (name "/BTN") (class "Default")
      (node (ref "D30") (pin "C") (pinfunction "C_C") (pintype "passive"))
      (node (ref "R72") (pin "2") (pinfunction "2_2") (pintype "passive"))
      (node (ref "R73") (pin "1") (pinfunction "1_1") (pintype "passive"))
    )
    (net (code "7") (name "/C0") (class "Default")
      (node (ref "CELLS") (pin "10") (pinfunction "10_10") (pintype "passive"))
      (node (ref "D7") (pin "A") (pinfunction "A_A") (pintype "passive"))
      (node (ref "K5") (pin "10") (pinfunction "10_10") (pintype "passive"))
      (node (ref "Q5") (pin "2") (pinfunction "S_2") (pintype "passive"))
      (node (ref "R35") (pin "1") (pinfunction "1_1") (pintype "passive"))
    )
    (net (code "8") (name "/C1") (class "Default")
      (node (ref "CELLS") (pin "2") (pinfunction "2_2") (pintype "passive"))
      (node (ref "D8") (pin "A") (pinfunction "A_A") (pintype "passive"))
      (node (ref "K5") (pin "2") (pinfunction "2_2") (pintype "passive"))
      (node (ref "Q6") (pin "2") (pinfunction "S_2") (pintype "passive"))
      (node (ref "R20") (pin "1") (pinfunction "1_1") (pintype "passive"))
      (node (ref "R36") (pin "1") (pinfunction "1_1") (pintype "passive"))
    )
    (net (code "9") (name "/C2") (class "Default")
      (node (ref "CELLS") (pin "11") (pinfunction "11_11") (pintype "passive"))
      (node (ref "D9") (pin "A") (pinfunction "A_A") (pintype "passive"))
      (node (ref "K5") (pin "11") (pinfunction "11_11") (pintype "passive"))
      (node (ref "Q7") (pin "2") (pinfunction "S_2") (pintype "passive"))
      (node (ref "R21") (pin "1") (pinfunction "1_1") (pintype "passive"))
      (node (ref "R37") (pin "1") (pinfunction "1_1") (pintype "passive"))
    )
    (net (code "10") (name "/C3") (class "Default")
      (node (ref "CELLS") (pin "3") (pinfunction "3_3") (pintype "passive"))
      (node (ref "D10") (pin "A") (pinfunction "A_A") (pintype "passive"))
      (node (ref "K5") (pin "3") (pinfunction "3_3") (pintype "passive"))
      (node (ref "Q8") (pin "2") (pinfunction "S_2") (pintype "passive"))
      (node (ref "R22") (pin "1") (pinfunction "1_1") (pintype "passive"))
      (node (ref "R38") (pin "1") (pinfunction "1_1") (pintype "passive"))
    )
    (net (code "11") (name "/C4") (class "Default")
      (node (ref "CELLS") (pin "12") (pinfunction "12_12") (pintype "passive"))
      (node (ref "D11") (pin "A") (pinfunction "A_A") (pintype "passive"))
      (node (ref "K5") (pin "12") (pinfunction "12_12") (pintype "passive"))
      (node (ref "Q9") (pin "2") (pinfunction "S_2") (pintype "passive"))
      (node (ref "R23") (pin "1") (pinfunction "1_1") (pintype "passive"))
      (node (ref "R39") (pin "1") (pinfunction "1_1") (pintype "passive"))
    )
    (net (code "12") (name "/C5") (class "Default")
      (node (ref "CELLS") (pin "4") (pinfunction "4_4") (pintype "passive"))
      (node (ref "D12") (pin "A") (pinfunction "A_A") (pintype "passive"))
      (node (ref "K5") (pin "4") (pinfunction "4_4") (pintype "passive"))
      (node (ref "Q10") (pin "2") (pinfunction "S_2") (pintype "passive"))
      (node (ref "R13") (pin "1") (pinfunction "1_1") (pintype "passive"))
      (node (ref "R24") (pin "1") (pinfunction "1_1") (pintype "passive"))
      (node (ref "R40") (pin "1") (pinfunction "1_1") (pintype "passive"))
      (node (ref "R41") (pin "1") (pinfunction "1_1") (pintype "passive"))
    )
    (net (code "13") (name "/C6") (class "Default")
      (node (ref "CELLS") (pin "13") (pinfunction "13_13") (pintype "passive"))
      (node (ref "D13") (pin "A") (pinfunction "A_A") (pintype "passive"))
      (node (ref "K5") (pin "13") (pinfunction "13_13") (pintype "passive"))
      (node (ref "Q11") (pin "2") (pinfunction "S_2") (pintype "passive"))
      (node (ref "R25") (pin "1") (pinfunction "1_1") (pintype "passive"))
      (node (ref "R42") (pin "1") (pinfunction "1_1") (pintype "passive"))
    )
    (net (code "14") (name "/C7") (class "Default")
      (node (ref "CELLS") (pin "5") (pinfunction "5_5") (pintype "passive"))
      (node (ref "D14") (pin "A") (pinfunction "A_A") (pintype "passive"))
      (node (ref "K5") (pin "5") (pinfunction "5_5") (pintype "passive"))
      (node (ref "Q12") (pin "2") (pinfunction "S_2") (pintype "passive"))
      (node (ref "R26") (pin "1") (pinfunction "1_1") (pintype "passive"))
      (node (ref "R43") (pin "1") (pinfunction "1_1") (pintype "passive"))
    )
    (net (code "15") (name "/C8") (class "Default")
      (node (ref "CELLS") (pin "14") (pinfunction "14_14") (pintype "passive"))
      (node (ref "D15") (pin "A") (pinfunction "A_A") (pintype "passive"))
      (node (ref "K5") (pin "14") (pinfunction "14_14") (pintype "passive"))
      (node (ref "Q13") (pin "2") (pinfunction "S_2") (pintype "passive"))
      (node (ref "R27") (pin "1") (pinfunction "1_1") (pintype "passive"))
      (node (ref "R44") (pin "1") (pinfunction "1_1") (pintype "passive"))
    )
    (net (code "16") (name "/C9") (class "Default")
      (node (ref "CELLS") (pin "6") (pinfunction "6_6") (pintype "passive"))
      (node (ref "D16") (pin "A") (pinfunction "A_A") (pintype "passive"))
      (node (ref "K5") (pin "6") (pinfunction "6_6") (pintype "passive"))
      (node (ref "Q14") (pin "2") (pinfunction "S_2") (pintype "passive"))
      (node (ref "R28") (pin "1") (pinfunction "1_1") (pintype "passive"))
      (node (ref "R45") (pin "1") (pinfunction "1_1") (pintype "passive"))
    )
    (net (code "17") (name "/C10") (class "Default")
      (node (ref "CELLS") (pin "15") (pinfunction "15_15") (pintype "passive"))
      (node (ref "D17") (pin "A") (pinfunction "A_A") (pintype "passive"))
      (node (ref "K5") (pin "15") (pinfunction "15_15") (pintype "passive"))
      (node (ref "Q15") (pin "2") (pinfunction "S_2") (pintype "passive"))
      (node (ref "R12") (pin "1") (pinfunction "1_1") (pintype "passive"))
      (node (ref "R29") (pin "1") (pinfunction "1_1") (pintype "passive"))
      (node (ref "R46") (pin "1") (pinfunction "1_1") (pintype "passive"))
      (node (ref "R47") (pin "1") (pinfunction "1_1") (pintype "passive"))
    )
    (net (code "18") (name "/C11") (class "Default")
      (node (ref "CELLS") (pin "7") (pinfunction "7_7") (pintype "passive"))
      (node (ref "D18") (pin "A") (pinfunction "A_A") (pintype "passive"))
      (node (ref "K5") (pin "7") (pinfunction "7_7") (pintype "passive"))
      (node (ref "Q16") (pin "2") (pinfunction "S_2") (pintype "passive"))
      (node (ref "R30") (pin "1") (pinfunction "1_1") (pintype "passive"))
      (node (ref "R48") (pin "1") (pinfunction "1_1") (pintype "passive"))
    )
    (net (code "19") (name "/C12") (class "Default")
      (node (ref "CELLS") (pin "16") (pinfunction "16_16") (pintype "passive"))
      (node (ref "D19") (pin "A") (pinfunction "A_A") (pintype "passive"))
      (node (ref "K5") (pin "16") (pinfunction "16_16") (pintype "passive"))
      (node (ref "Q17") (pin "2") (pinfunction "S_2") (pintype "passive"))
      (node (ref "R31") (pin "1") (pinfunction "1_1") (pintype "passive"))
      (node (ref "R49") (pin "1") (pinfunction "1_1") (pintype "passive"))
    )
    (net (code "20") (name "/C13") (class "Default")
      (node (ref "CELLS") (pin "8") (pinfunction "8_8") (pintype "passive"))
      (node (ref "D20") (pin "A") (pinfunction "A_A") (pintype "passive"))
      (node (ref "K5") (pin "8") (pinfunction "8_8") (pintype "passive"))
      (node (ref "Q18") (pin "2") (pinfunction "S_2") (pintype "passive"))
      (node (ref "R32") (pin "1") (pinfunction "1_1") (pintype "passive"))
      (node (ref "R50") (pin "1") (pinfunction "1_1") (pintype "passive"))
    )
    (net (code "21") (name "/C14") (class "Default")
      (node (ref "CELLS") (pin "17") (pinfunction "17_17") (pintype "passive"))
      (node (ref "D21") (pin "A") (pinfunction "A_A") (pintype "passive"))
      (node (ref "K5") (pin "17") (pinfunction "17_17") (pintype "passive"))
      (node (ref "Q19") (pin "2") (pinfunction "S_2") (pintype "passive"))
      (node (ref "R33") (pin "1") (pinfunction "1_1") (pintype "passive"))
      (node (ref "R51") (pin "1") (pinfunction "1_1") (pintype "passive"))
    )
    (net (code "22") (name "/C15") (class "Default")
      (node (ref "CELLS") (pin "9") (pinfunction "9_9") (pintype "passive"))
      (node (ref "K5") (pin "9") (pinfunction "9_9") (pintype "passive"))
      (node (ref "R34") (pin "1") (pinfunction "1_1") (pintype "passive"))
      (node (ref "R52") (pin "1") (pinfunction "1_1") (pintype "passive"))
    )
    (net (code "23") (name "/CAP1") (class "Default")
      (node (ref "C14") (pin "1") (pinfunction "1_1") (pintype "passive"))
      (node (ref "IC1") (pin "7") (pinfunction "CAP1_7") (pintype "output"))
    )
    (net (code "24") (name "/CAP2") (class "Default")
      (node (ref "C16") (pin "1") (pinfunction "1_1") (pintype "passive"))
      (node (ref "IC1") (pin "11") (pinfunction "NC11_11") (pintype "passive"))
      (node (ref "IC1") (pin "12") (pinfunction "NC12_12") (pintype "passive"))
      (node (ref "IC1") (pin "14") (pinfunction "CAP2_14") (pintype "output"))
    )
    (net (code "25") (name "/CAP3") (class "Default")
      (node (ref "C18") (pin "1") (pinfunction "1_1") (pintype "passive"))
      (node (ref "IC1") (pin "16") (pinfunction "NC16_16") (pintype "passive"))
      (node (ref "IC1") (pin "17") (pinfunction "NC17_17") (pintype "passive"))
      (node (ref "IC1") (pin "19") (pinfunction "CAP3_19") (pintype "output"))
    )
    (net (code "26") (name "/CHG_EN") (class "Default")
      (node (ref "IC1") (pin "2") (pinfunction "CHG_2") (pintype "output"))
      (node (ref "JP5") (pin "2") (pinfunction "2_2") (pintype "passive"))
    )
    (net (code "27") (name "/DSG_EN") (class "Default")
      (node (ref "IC1") (pin "1") (pinfunction "DSG_1") (pintype "output"))
      (node (ref "JP5") (pin "4") (pinfunction "4_4") (pintype "passive"))
    )
    (net (code "28") (name "/I2C2_SCL") (class "Default")
      (node (ref "IC1") (pin "5") (pinfunction "SCL_5") (pintype "passive"))
    )
    (net (code "29") (name "/I2C2_SDA") (class "Default")
      (node (ref "IC1") (pin "4") (pinfunction "SDA_4") (pintype "passive"))
    )
    (net (code "30") (name "/LOAD+") (class "Default")
      (node (ref "JP5") (pin "3") (pinfunction "3_3") (pintype "passive"))
      (node (ref "R79") (pin "2") (pinfunction "2_2") (pintype "passive"))
    )
    (net (code "31") (name "/MCU_IN") (class "Default")
      (node (ref "D29") (pin "A") (pinfunction "A_A") (pintype "passive"))
      (node (ref "K1") (pin "1") (pinfunction "1_1") (pintype "passive"))
      (node (ref "R73") (pin "2") (pinfunction "2_2") (pintype "passive"))
      (node (ref "S1") (pin "2") (pinfunction "2_2") (pintype "passive"))
      (node (ref "S1") (pin "4") (pinfunction "4_4") (pintype "passive"))
    )
    (net (code "32") (name "/PCHG_EN") (class "Default")
      (node (ref "JP5") (pin "6") (pinfunction "6_6") (pintype "passive"))
    )
    (net (code "33") (name "/PWR") (class "Default")
      (node (ref "CELLS") (pin "18") (pinfunction "18_18") (pintype "passive"))
      (node (ref "D6") (pin "A") (pinfunction "A_A") (pintype "passive"))
      (node (ref "K5") (pin "18") (pinfunction "18_18") (pintype "passive"))
      (node (ref "R11") (pin "1") (pinfunction "1_1") (pintype "passive"))
      (node (ref "R6") (pin "1") (pinfunction "1_1") (pintype "passive"))
      (node (ref "R77") (pin "2") (pinfunction "2_2") (pintype "passive"))
    )
    (net (code "34") (name "/REGOUT") (class "Default")
      (node (ref "C10") (pin "1") (pinfunction "1_1") (pintype "passive"))
      (node (ref "IC1") (pin "8") (pinfunction "REGOUT_8") (pintype "power_in"))
    )
    (net (code "35") (name "/REGSRC") (class "Default")
      (node (ref "C11") (pin "1") (pinfunction "1_1") (pintype "passive"))
      (node (ref "IC1") (pin "9") (pinfunction "REGSRC_9") (pintype "passive"))
      (node (ref "Q4") (pin "2") (pinfunction "S_2") (pintype "passive"))
    )
    (net (code "36") (name "/R_SENSE+") (class "Default")
      (node (ref "JP5") (pin "7") (pinfunction "7_7") (pintype "passive"))
      (node (ref "R8") (pin "1") (pinfunction "1_1") (pintype "passive"))
    )
    (net (code "37") (name "/R_SENSE-") (class "Default")
      (node (ref "JP5") (pin "8") (pinfunction "8_8") (pintype "passive"))
      (node (ref "R9") (pin "1") (pinfunction "1_1") (pintype "passive"))
    )
    (net (code "38") (name "/SRN") (class "Default")
      (node (ref "C4") (pin "2") (pinfunction "2_2") (pintype "passive"))
      (node (ref "C6") (pin "1") (pinfunction "1_1") (pintype "passive"))
      (node (ref "D28") (pin "C") (pinfunction "C_C") (pintype "passive"))
      (node (ref "IC1") (pin "43") (pinfunction "SRN_43") (pintype "passive"))
      (node (ref "R9") (pin "2") (pinfunction "2_2") (pintype "passive"))
    )
    (net (code "39") (name "/SRP") (class "Default")
      (node (ref "C4") (pin "1") (pinfunction "1_1") (pintype "passive"))
      (node (ref "C5") (pin "1") (pinfunction "1_1") (pintype "passive"))
      (node (ref "D27") (pin "C") (pinfunction "C_C") (pintype "passive"))
      (node (ref "IC1") (pin "42") (pinfunction "SRP_42") (pintype "passive"))
      (node (ref "R8") (pin "2") (pinfunction "2_2") (pintype "passive"))
    )
    (net (code "40") (name "/TS1") (class "Default")
      (node (ref "C13") (pin "1") (pinfunction "1_1") (pintype "passive"))
      (node (ref "IC1") (pin "6") (pinfunction "TS1_6") (pintype "passive"))
      (node (ref "K4") (pin "4") (pinfunction "4_4") (pintype "passive"))
      (node (ref "R15") (pin "1") (pinfunction "1_1") (pintype "passive"))
      (node (ref "TEMP") (pin "4") (pinfunction "4_4") (pintype "passive"))
    )
    (net (code "41") (name "/TS2") (class "Default")
      (node (ref "C15") (pin "1") (pinfunction "1_1") (pintype "passive"))
      (node (ref "IC1") (pin "13") (pinfunction "TS2_13") (pintype "passive"))
      (node (ref "K4") (pin "5") (pinfunction "5_5") (pintype "passive"))
      (node (ref "TEMP") (pin "5") (pinfunction "5_5") (pintype "passive"))
    )
    (net (code "42") (name "/TS3") (class "Default")
      (node (ref "C17") (pin "1") (pinfunction "1_1") (pintype "passive"))
      (node (ref "IC1") (pin "18") (pinfunction "TS3_18") (pintype "passive"))
      (node (ref "K4") (pin "6") (pinfunction "6_6") (pintype "passive"))
      (node (ref "TEMP") (pin "6") (pinfunction "6_6") (pintype "passive"))
    )
    (net (code "43") (name "/VC0") (class "Default")
      (node (ref "C37") (pin "1") (pinfunction "1_1") (pintype "passive"))
      (node (ref "D5") (pin "C") (pinfunction "C_C") (pintype "passive"))
      (node (ref "IC1") (pin "41") (pinfunction "VC0_41") (pintype "passive"))
      (node (ref "R35") (pin "2") (pinfunction "2_2") (pintype "passive"))
      (node (ref "R53") (pin "1") (pinfunction "1_1") (pintype "passive"))
    )
    (net (code "44") (name "/VC1") (class "Default")
      (node (ref "C22") (pin "1") (pinfunction "1_1") (pintype "passive"))
      (node (ref "C23") (pin "2") (pinfunction "2_2") (pintype "passive"))
      (node (ref "IC1") (pin "40") (pinfunction "VC1_40") (pintype "passive"))
      (node (ref "K1") (pin "2") (pinfunction "2_2") (pintype "passive"))
      (node (ref "R36") (pin "2") (pinfunction "2_2") (pintype "passive"))
      (node (ref "R54") (pin "1") (pinfunction "1_1") (pintype "passive"))
      (node (ref "S1") (pin "1") (pinfunction "1_1") (pintype "passive"))
      (node (ref "S1") (pin "3") (pinfunction "3_3") (pintype "passive"))
    )
    (net (code "45") (name "/VC2") (class "Default")
      (node (ref "C23") (pin "1") (pinfunction "1_1") (pintype "passive"))
      (node (ref "C24") (pin "2") (pinfunction "2_2") (pintype "passive"))
      (node (ref "IC1") (pin "39") (pinfunction "VC2_39") (pintype "passive"))
      (node (ref "R37") (pin "2") (pinfunction "2_2") (pintype "passive"))
      (node (ref "R55") (pin "1") (pinfunction "1_1") (pintype "passive"))
    )
    (net (code "46") (name "/VC3") (class "Default")
      (node (ref "C24") (pin "1") (pinfunction "1_1") (pintype "passive"))
      (node (ref "C25") (pin "2") (pinfunction "2_2") (pintype "passive"))
      (node (ref "IC1") (pin "38") (pinfunction "VC3_38") (pintype "passive"))
      (node (ref "R38") (pin "2") (pinfunction "2_2") (pintype "passive"))
      (node (ref "R56") (pin "1") (pinfunction "1_1") (pintype "passive"))
    )
    (net (code "47") (name "/VC4") (class "Default")
      (node (ref "C25") (pin "1") (pinfunction "1_1") (pintype "passive"))
      (node (ref "C26") (pin "2") (pinfunction "2_2") (pintype "passive"))
      (node (ref "IC1") (pin "37") (pinfunction "VC4_37") (pintype "passive"))
      (node (ref "R39") (pin "2") (pinfunction "2_2") (pintype "passive"))
      (node (ref "R57") (pin "1") (pinfunction "1_1") (pintype "passive"))
    )
    (net (code "48") (name "/VC5") (class "Default")
      (node (ref "C26") (pin "1") (pinfunction "1_1") (pintype "passive"))
      (node (ref "D2") (pin "A") (pinfunction "A_A") (pintype "passive"))
      (node (ref "IC1") (pin "36") (pinfunction "VC5_36") (pintype "passive"))
      (node (ref "R40") (pin "2") (pinfunction "2_2") (pintype "passive"))
    )
    (net (code "49") (name "/VC5B") (class "Default")
      (node (ref "C38") (pin "2") (pinfunction "2_2") (pintype "passive"))
      (node (ref "IC1") (pin "35") (pinfunction "VC5B_35") (pintype "passive"))
      (node (ref "R41") (pin "2") (pinfunction "2_2") (pintype "passive"))
      (node (ref "R58") (pin "1") (pinfunction "1_1") (pintype "passive"))
    )
    (net (code "50") (name "/VC5X") (class "Default")
      (node (ref "C12") (pin "1") (pinfunction "1_1") (pintype "passive"))
      (node (ref "C15") (pin "2") (pinfunction "2_2") (pintype "passive"))
      (node (ref "C16") (pin "2") (pinfunction "2_2") (pintype "passive"))
      (node (ref "C27") (pin "2") (pinfunction "2_2") (pintype "passive"))
      (node (ref "C38") (pin "1") (pinfunction "1_1") (pintype "passive"))
      (node (ref "C9") (pin "2") (pinfunction "2_2") (pintype "passive"))
      (node (ref "D2") (pin "C") (pinfunction "C_C") (pintype "passive"))
      (node (ref "IC1") (pin "10") (pinfunction "VC5X_10") (pintype "power_in"))
      (node (ref "K4") (pin "2") (pinfunction "2_2") (pintype "passive"))
      (node (ref "R13") (pin "2") (pinfunction "2_2") (pintype "passive"))
      (node (ref "R14") (pin "1") (pinfunction "1_1") (pintype "passive"))
      (node (ref "TEMP") (pin "2") (pinfunction "2_2") (pintype "passive"))
    )
    (net (code "51") (name "/VC6") (class "Default")
      (node (ref "C27") (pin "1") (pinfunction "1_1") (pintype "passive"))
      (node (ref "C28") (pin "2") (pinfunction "2_2") (pintype "passive"))
      (node (ref "IC1") (pin "34") (pinfunction "VC6_34") (pintype "passive"))
      (node (ref "R42") (pin "2") (pinfunction "2_2") (pintype "passive"))
      (node (ref "R59") (pin "1") (pinfunction "1_1") (pintype "passive"))
    )
    (net (code "52") (name "/VC7") (class "Default")
      (node (ref "C28") (pin "1") (pinfunction "1_1") (pintype "passive"))
      (node (ref "C29") (pin "2") (pinfunction "2_2") (pintype "passive"))
      (node (ref "IC1") (pin "33") (pinfunction "VC7_33") (pintype "passive"))
      (node (ref "R43") (pin "2") (pinfunction "2_2") (pintype "passive"))
      (node (ref "R60") (pin "1") (pinfunction "1_1") (pintype "passive"))
    )
    (net (code "53") (name "/VC8") (class "Default")
      (node (ref "C29") (pin "1") (pinfunction "1_1") (pintype "passive"))
      (node (ref "C30") (pin "2") (pinfunction "2_2") (pintype "passive"))
      (node (ref "IC1") (pin "32") (pinfunction "VC8_32") (pintype "passive"))
      (node (ref "R44") (pin "2") (pinfunction "2_2") (pintype "passive"))
      (node (ref "R61") (pin "1") (pinfunction "1_1") (pintype "passive"))
    )
    (net (code "54") (name "/VC9") (class "Default")
      (node (ref "C30") (pin "1") (pinfunction "1_1") (pintype "passive"))
      (node (ref "C31") (pin "2") (pinfunction "2_2") (pintype "passive"))
      (node (ref "IC1") (pin "31") (pinfunction "VC9_31") (pintype "passive"))
      (node (ref "R45") (pin "2") (pinfunction "2_2") (pintype "passive"))
      (node (ref "R62") (pin "1") (pinfunction "1_1") (pintype "passive"))
    )
    (net (code "55") (name "/VC10") (class "Default")
      (node (ref "C31") (pin "1") (pinfunction "1_1") (pintype "passive"))
      (node (ref "D3") (pin "A") (pinfunction "A_A") (pintype "passive"))
      (node (ref "IC1") (pin "30") (pinfunction "VC10_30") (pintype "passive"))
      (node (ref "R46") (pin "2") (pinfunction "2_2") (pintype "passive"))
    )
    (net (code "56") (name "/VC10B") (class "Default")
      (node (ref "C39") (pin "2") (pinfunction "2_2") (pintype "passive"))
      (node (ref "IC1") (pin "29") (pinfunction "VC10B_29") (pintype "passive"))
      (node (ref "R47") (pin "2") (pinfunction "2_2") (pintype "passive"))
      (node (ref "R63") (pin "1") (pinfunction "1_1") (pintype "passive"))
    )
    (net (code "57") (name "/VC10X") (class "Default")
      (node (ref "C17") (pin "2") (pinfunction "2_2") (pintype "passive"))
      (node (ref "C18") (pin "2") (pinfunction "2_2") (pintype "passive"))
      (node (ref "C32") (pin "2") (pinfunction "2_2") (pintype "passive"))
      (node (ref "C39") (pin "1") (pinfunction "1_1") (pintype "passive"))
      (node (ref "C8") (pin "2") (pinfunction "2_2") (pintype "passive"))
      (node (ref "C9") (pin "1") (pinfunction "1_1") (pintype "passive"))
      (node (ref "D3") (pin "C") (pinfunction "C_C") (pintype "passive"))
      (node (ref "IC1") (pin "15") (pinfunction "VC10X_15") (pintype "power_in"))
      (node (ref "K4") (pin "3") (pinfunction "3_3") (pintype "passive"))
      (node (ref "R12") (pin "2") (pinfunction "2_2") (pintype "passive"))
      (node (ref "TEMP") (pin "3") (pinfunction "3_3") (pintype "passive"))
    )
    (net (code "58") (name "/VC11") (class "Default")
      (node (ref "C32") (pin "1") (pinfunction "1_1") (pintype "passive"))
      (node (ref "C33") (pin "2") (pinfunction "2_2") (pintype "passive"))
      (node (ref "IC1") (pin "28") (pinfunction "VC11_28") (pintype "passive"))
      (node (ref "R48") (pin "2") (pinfunction "2_2") (pintype "passive"))
      (node (ref "R64") (pin "1") (pinfunction "1_1") (pintype "passive"))
    )
    (net (code "59") (name "/VC12") (class "Default")
      (node (ref "C33") (pin "1") (pinfunction "1_1") (pintype "passive"))
      (node (ref "C34") (pin "2") (pinfunction "2_2") (pintype "passive"))
      (node (ref "IC1") (pin "27") (pinfunction "VC12_27") (pintype "passive"))
      (node (ref "R49") (pin "2") (pinfunction "2_2") (pintype "passive"))
      (node (ref "R65") (pin "1") (pinfunction "1_1") (pintype "passive"))
    )
    (net (code "60") (name "/VC13") (class "Default")
      (node (ref "C34") (pin "1") (pinfunction "1_1") (pintype "passive"))
      (node (ref "C35") (pin "2") (pinfunction "2_2") (pintype "passive"))
      (node (ref "IC1") (pin "26") (pinfunction "VC13_26") (pintype "passive"))
      (node (ref "R50") (pin "2") (pinfunction "2_2") (pintype "passive"))
      (node (ref "R66") (pin "1") (pinfunction "1_1") (pintype "passive"))
    )
    (net (code "61") (name "/VC14") (class "Default")
      (node (ref "C35") (pin "1") (pinfunction "1_1") (pintype "passive"))
      (node (ref "C36") (pin "2") (pinfunction "2_2") (pintype "passive"))
      (node (ref "IC1") (pin "25") (pinfunction "VC14_25") (pintype "passive"))
      (node (ref "R51") (pin "2") (pinfunction "2_2") (pintype "passive"))
      (node (ref "R67") (pin "1") (pinfunction "1_1") (pintype "passive"))
    )
    (net (code "62") (name "/VC15") (class "Default")
      (node (ref "C36") (pin "1") (pinfunction "1_1") (pintype "passive"))
      (node (ref "D4") (pin "A") (pinfunction "A_A") (pintype "passive"))
      (node (ref "IC1") (pin "24") (pinfunction "VC15_24") (pintype "passive"))
      (node (ref "R52") (pin "2") (pinfunction "2_2") (pintype "passive"))
    )
    (net (code "63") (name "/V_BAT") (class "Default")
      (node (ref "C19") (pin "1") (pinfunction "1_1") (pintype "passive"))
      (node (ref "R77") (pin "1") (pinfunction "1_1") (pintype "passive"))
      (node (ref "R78") (pin "2") (pinfunction "2_2") (pintype "passive"))
    )
    (net (code "64") (name "/V_LOAD") (class "Default")
      (node (ref "C7") (pin "1") (pinfunction "1_1") (pintype "passive"))
      (node (ref "R79") (pin "1") (pinfunction "1_1") (pintype "passive"))
      (node (ref "R80") (pin "2") (pinfunction "2_2") (pintype "passive"))
    )
    (net (code "65") (name "GND") (class "Default")
      (node (ref "C10") (pin "2") (pinfunction "2_2") (pintype "passive"))
      (node (ref "C11") (pin "2") (pinfunction "2_2") (pintype "passive"))
      (node (ref "C12") (pin "2") (pinfunction "2_2") (pintype "passive"))
      (node (ref "C13") (pin "2") (pinfunction "2_2") (pintype "passive"))
      (node (ref "C14") (pin "2") (pinfunction "2_2") (pintype "passive"))
      (node (ref "C19") (pin "2") (pinfunction "2_2") (pintype "passive"))
      (node (ref "C22") (pin "2") (pinfunction "2_2") (pintype "passive"))
      (node (ref "C37") (pin "2") (pinfunction "2_2") (pintype "passive"))
      (node (ref "C5") (pin "2") (pinfunction "2_2") (pintype "passive"))
      (node (ref "C6") (pin "2") (pinfunction "2_2") (pintype "passive"))
      (node (ref "C7") (pin "2") (pinfunction "2_2") (pintype "passive"))
      (node (ref "CELLS") (pin "1") (pinfunction "1_1") (pintype "passive"))
      (node (ref "D27") (pin "A") (pinfunction "A_A") (pintype "passive"))
      (node (ref "D28") (pin "A") (pinfunction "A_A") (pintype "passive"))
      (node (ref "D30") (pin "A") (pinfunction "A_A") (pintype "passive"))
      (node (ref "D5") (pin "A") (pinfunction "A_A") (pintype "passive"))
      (node (ref "IC1") (pin "3") (pinfunction "VSS_3") (pintype "power_in"))
      (node (ref "K4") (pin "1") (pinfunction "1_1") (pintype "passive"))
      (node (ref "K5") (pin "1") (pinfunction "1_1") (pintype "passive"))
      (node (ref "R72") (pin "1") (pinfunction "1_1") (pintype "passive"))
      (node (ref "R76") (pin "1") (pinfunction "1_1") (pintype "passive"))
      (node (ref "R78") (pin "1") (pinfunction "1_1") (pintype "passive"))
      (node (ref "R80") (pin "1") (pinfunction "1_1") (pintype "passive"))
      (node (ref "TEMP") (pin "1") (pinfunction "1_1") (pintype "passive"))
    )
    (net (code "66") (name "Net-(D29-PadC)") (class "Default")
      (node (ref "D29") (pin "C") (pinfunction "C_C") (pintype "passive"))
      (node (ref "R15") (pin "2") (pinfunction "2_2") (pintype "passive"))
    )
    (net (code "67") (name "Net-(Q4-D)") (class "Default")
      (node (ref "D6") (pin "C") (pinfunction "C_C") (pintype "passive"))
      (node (ref "Q4") (pin "3") (pinfunction "D_3") (pintype "passive"))
      (node (ref "R6") (pin "2") (pinfunction "2_2") (pintype "passive"))
    )
    (net (code "68") (name "Net-(Q4-G)") (class "Default")
      (node (ref "Q4") (pin "1") (pinfunction "G_1") (pintype "passive"))
      (node (ref "R14") (pin "2") (pinfunction "2_2") (pintype "passive"))
    )
    (net (code "69") (name "Net-(Q5-D)") (class "Default")
      (node (ref "Q5") (pin "3") (pinfunction "D_3") (pintype "passive"))
      (node (ref "R20") (pin "2") (pinfunction "2_2") (pintype "passive"))
    )
    (net (code "70") (name "Net-(Q5-G)") (class "Default")
      (node (ref "D7") (pin "C") (pinfunction "C_C") (pintype "passive"))
      (node (ref "Q5") (pin "1") (pinfunction "G_1") (pintype "passive"))
      (node (ref "R53") (pin "2") (pinfunction "2_2") (pintype "passive"))
    )
    (net (code "71") (name "Net-(Q6-D)") (class "Default")
      (node (ref "Q6") (pin "3") (pinfunction "D_3") (pintype "passive"))
      (node (ref "R21") (pin "2") (pinfunction "2_2") (pintype "passive"))
    )
    (net (code "72") (name "Net-(Q6-G)") (class "Default")
      (node (ref "D8") (pin "C") (pinfunction "C_C") (pintype "passive"))
      (node (ref "Q6") (pin "1") (pinfunction "G_1") (pintype "passive"))
      (node (ref "R54") (pin "2") (pinfunction "2_2") (pintype "passive"))
    )
    (net (code "73") (name "Net-(Q7-D)") (class "Default")
      (node (ref "Q7") (pin "3") (pinfunction "D_3") (pintype "passive"))
      (node (ref "R22") (pin "2") (pinfunction "2_2") (pintype "passive"))
    )
    (net (code "74") (name "Net-(Q7-G)") (class "Default")
      (node (ref "D9") (pin "C") (pinfunction "C_C") (pintype "passive"))
      (node (ref "Q7") (pin "1") (pinfunction "G_1") (pintype "passive"))
      (node (ref "R55") (pin "2") (pinfunction "2_2") (pintype "passive"))
    )
    (net (code "75") (name "Net-(Q8-D)") (class "Default")
      (node (ref "Q8") (pin "3") (pinfunction "D_3") (pintype "passive"))
      (node (ref "R23") (pin "2") (pinfunction "2_2") (pintype "passive"))
    )
    (net (code "76") (name "Net-(Q8-G)") (class "Default")
      (node (ref "D10") (pin "C") (pinfunction "C_C") (pintype "passive"))
      (node (ref "Q8") (pin "1") (pinfunction "G_1") (pintype "passive"))
      (node (ref "R56") (pin "2") (pinfunction "2_2") (pintype "passive"))
    )
    (net (code "77") (name "Net-(Q9-D)") (class "Default")
      (node (ref "Q9") (pin "3") (pinfunction "D_3") (pintype "passive"))
      (node (ref "R24") (pin "2") (pinfunction "2_2") (pintype "passive"))
    )
    (net (code "78") (name "Net-(Q9-G)") (class "Default")
      (node (ref "D11") (pin "C") (pinfunction "C_C") (pintype "passive"))
      (node (ref "Q9") (pin "1") (pinfunction "G_1") (pintype "passive"))
      (node (ref "R57") (pin "2") (pinfunction "2_2") (pintype "passive"))
    )
    (net (code "79") (name "Net-(Q10-D)") (class "Default")
      (node (ref "Q10") (pin "3") (pinfunction "D_3") (pintype "passive"))
      (node (ref "R25") (pin "2") (pinfunction "2_2") (pintype "passive"))
    )
    (net (code "80") (name "Net-(Q10-G)") (class "Default")
      (node (ref "D12") (pin "C") (pinfunction "C_C") (pintype "passive"))
      (node (ref "Q10") (pin "1") (pinfunction "G_1") (pintype "passive"))
      (node (ref "R58") (pin "2") (pinfunction "2_2") (pintype "passive"))
    )
    (net (code "81") (name "Net-(Q11-D)") (class "Default")
      (node (ref "Q11") (pin "3") (pinfunction "D_3") (pintype "passive"))
      (node (ref "R26") (pin "2") (pinfunction "2_2") (pintype "passive"))
    )
    (net (code "82") (name "Net-(Q11-G)") (class "Default")
      (node (ref "D13") (pin "C") (pinfunction "C_C") (pintype "passive"))
      (node (ref "Q11") (pin "1") (pinfunction "G_1") (pintype "passive"))
      (node (ref "R59") (pin "2") (pinfunction "2_2") (pintype "passive"))
    )
    (net (code "83") (name "Net-(Q12-D)") (class "Default")
      (node (ref "Q12") (pin "3") (pinfunction "D_3") (pintype "passive"))
      (node (ref "R27") (pin "2") (pinfunction "2_2") (pintype "passive"))
    )
    (net (code "84") (name "Net-(Q12-G)") (class "Default")
      (node (ref "D14") (pin "C") (pinfunction "C_C") (pintype "passive"))
      (node (ref "Q12") (pin "1") (pinfunction "G_1") (pintype "passive"))
      (node (ref "R60") (pin "2") (pinfunction "2_2") (pintype "passive"))
    )
    (net (code "85") (name "Net-(Q13-D)") (class "Default")
      (node (ref "Q13") (pin "3") (pinfunction "D_3") (pintype "passive"))
      (node (ref "R28") (pin "2") (pinfunction "2_2") (pintype "passive"))
    )
    (net (code "86") (name "Net-(Q13-G)") (class "Default")
      (node (ref "D15") (pin "C") (pinfunction "C_C") (pintype "passive"))
      (node (ref "Q13") (pin "1") (pinfunction "G_1") (pintype "passive"))
      (node (ref "R61") (pin "2") (pinfunction "2_2") (pintype "passive"))
    )
    (net (code "87") (name "Net-(Q14-D)") (class "Default")
      (node (ref "Q14") (pin "3") (pinfunction "D_3") (pintype "passive"))
      (node (ref "R29") (pin "2") (pinfunction "2_2") (pintype "passive"))
    )
    (net (code "88") (name "Net-(Q14-G)") (class "Default")
      (node (ref "D16") (pin "C") (pinfunction "C_C") (pintype "passive"))
      (node (ref "Q14") (pin "1") (pinfunction "G_1") (pintype "passive"))
      (node (ref "R62") (pin "2") (pinfunction "2_2") (pintype "passive"))
    )
    (net (code "89") (name "Net-(Q15-D)") (class "Default")
      (node (ref "Q15") (pin "3") (pinfunction "D_3") (pintype "passive"))
      (node (ref "R30") (pin "2") (pinfunction "2_2") (pintype "passive"))
    )
    (net (code "90") (name "Net-(Q15-G)") (class "Default")
      (node (ref "D17") (pin "C") (pinfunction "C_C") (pintype "passive"))
      (node (ref "Q15") (pin "1") (pinfunction "G_1") (pintype "passive"))
      (node (ref "R63") (pin "2") (pinfunction "2_2") (pintype "passive"))
    )
    (net (code "91") (name "Net-(Q16-D)") (class "Default")
      (node (ref "Q16") (pin "3") (pinfunction "D_3") (pintype "passive"))
      (node (ref "R31") (pin "2") (pinfunction "2_2") (pintype "passive"))
    )
    (net (code "92") (name "Net-(Q16-G)") (class "Default")
      (node (ref "D18") (pin "C") (pinfunction "C_C") (pintype "passive"))
      (node (ref "Q16") (pin "1") (pinfunction "G_1") (pintype "passive"))
      (node (ref "R64") (pin "2") (pinfunction "2_2") (pintype "passive"))
    )
    (net (code "93") (name "Net-(Q17-D)") (class "Default")
      (node (ref "Q17") (pin "3") (pinfunction "D_3") (pintype "passive"))
      (node (ref "R32") (pin "2") (pinfunction "2_2") (pintype "passive"))
    )
    (net (code "94") (name "Net-(Q17-G)") (class "Default")
      (node (ref "D19") (pin "C") (pinfunction "C_C") (pintype "passive"))
      (node (ref "Q17") (pin "1") (pinfunction "G_1") (pintype "passive"))
      (node (ref "R65") (pin "2") (pinfunction "2_2") (pintype "passive"))
    )
    (net (code "95") (name "Net-(Q18-D)") (class "Default")
      (node (ref "Q18") (pin "3") (pinfunction "D_3") (pintype "passive"))
      (node (ref "R33") (pin "2") (pinfunction "2_2") (pintype "passive"))
    )
    (net (code "96") (name "Net-(Q18-G)") (class "Default")
      (node (ref "D20") (pin "C") (pinfunction "C_C") (pintype "passive"))
      (node (ref "Q18") (pin "1") (pinfunction "G_1") (pintype "passive"))
      (node (ref "R66") (pin "2") (pinfunction "2_2") (pintype "passive"))
    )
    (net (code "97") (name "Net-(Q19-D)") (class "Default")
      (node (ref "Q19") (pin "3") (pinfunction "D_3") (pintype "passive"))
      (node (ref "R34") (pin "2") (pinfunction "2_2") (pintype "passive"))
    )
    (net (code "98") (name "Net-(Q19-G)") (class "Default")
      (node (ref "D21") (pin "C") (pinfunction "C_C") (pintype "passive"))
      (node (ref "Q19") (pin "1") (pinfunction "G_1") (pintype "passive"))
      (node (ref "R67") (pin "2") (pinfunction "2_2") (pintype "passive"))
    )
    (net (code "99") (name "unconnected-(IC1-NC21-Pad21)") (class "Default")
      (node (ref "IC1") (pin "21") (pinfunction "NC21_21") (pintype "passive"))
    )
    (net (code "100") (name "unconnected-(IC1-NC22-Pad22)") (class "Default")
      (node (ref "IC1") (pin "22") (pinfunction "NC22_22") (pintype "passive"))
    )
    (net (code "101") (name "unconnected-(IC1-NC23-Pad23)") (class "Default")
      (node (ref "IC1") (pin "23") (pinfunction "NC23_23") (pintype "passive"))
    )
  )
)
